# SCH_URM07-Test_2025-04-24.net
KiCad netlist of a schematic drawn in EasyEDA
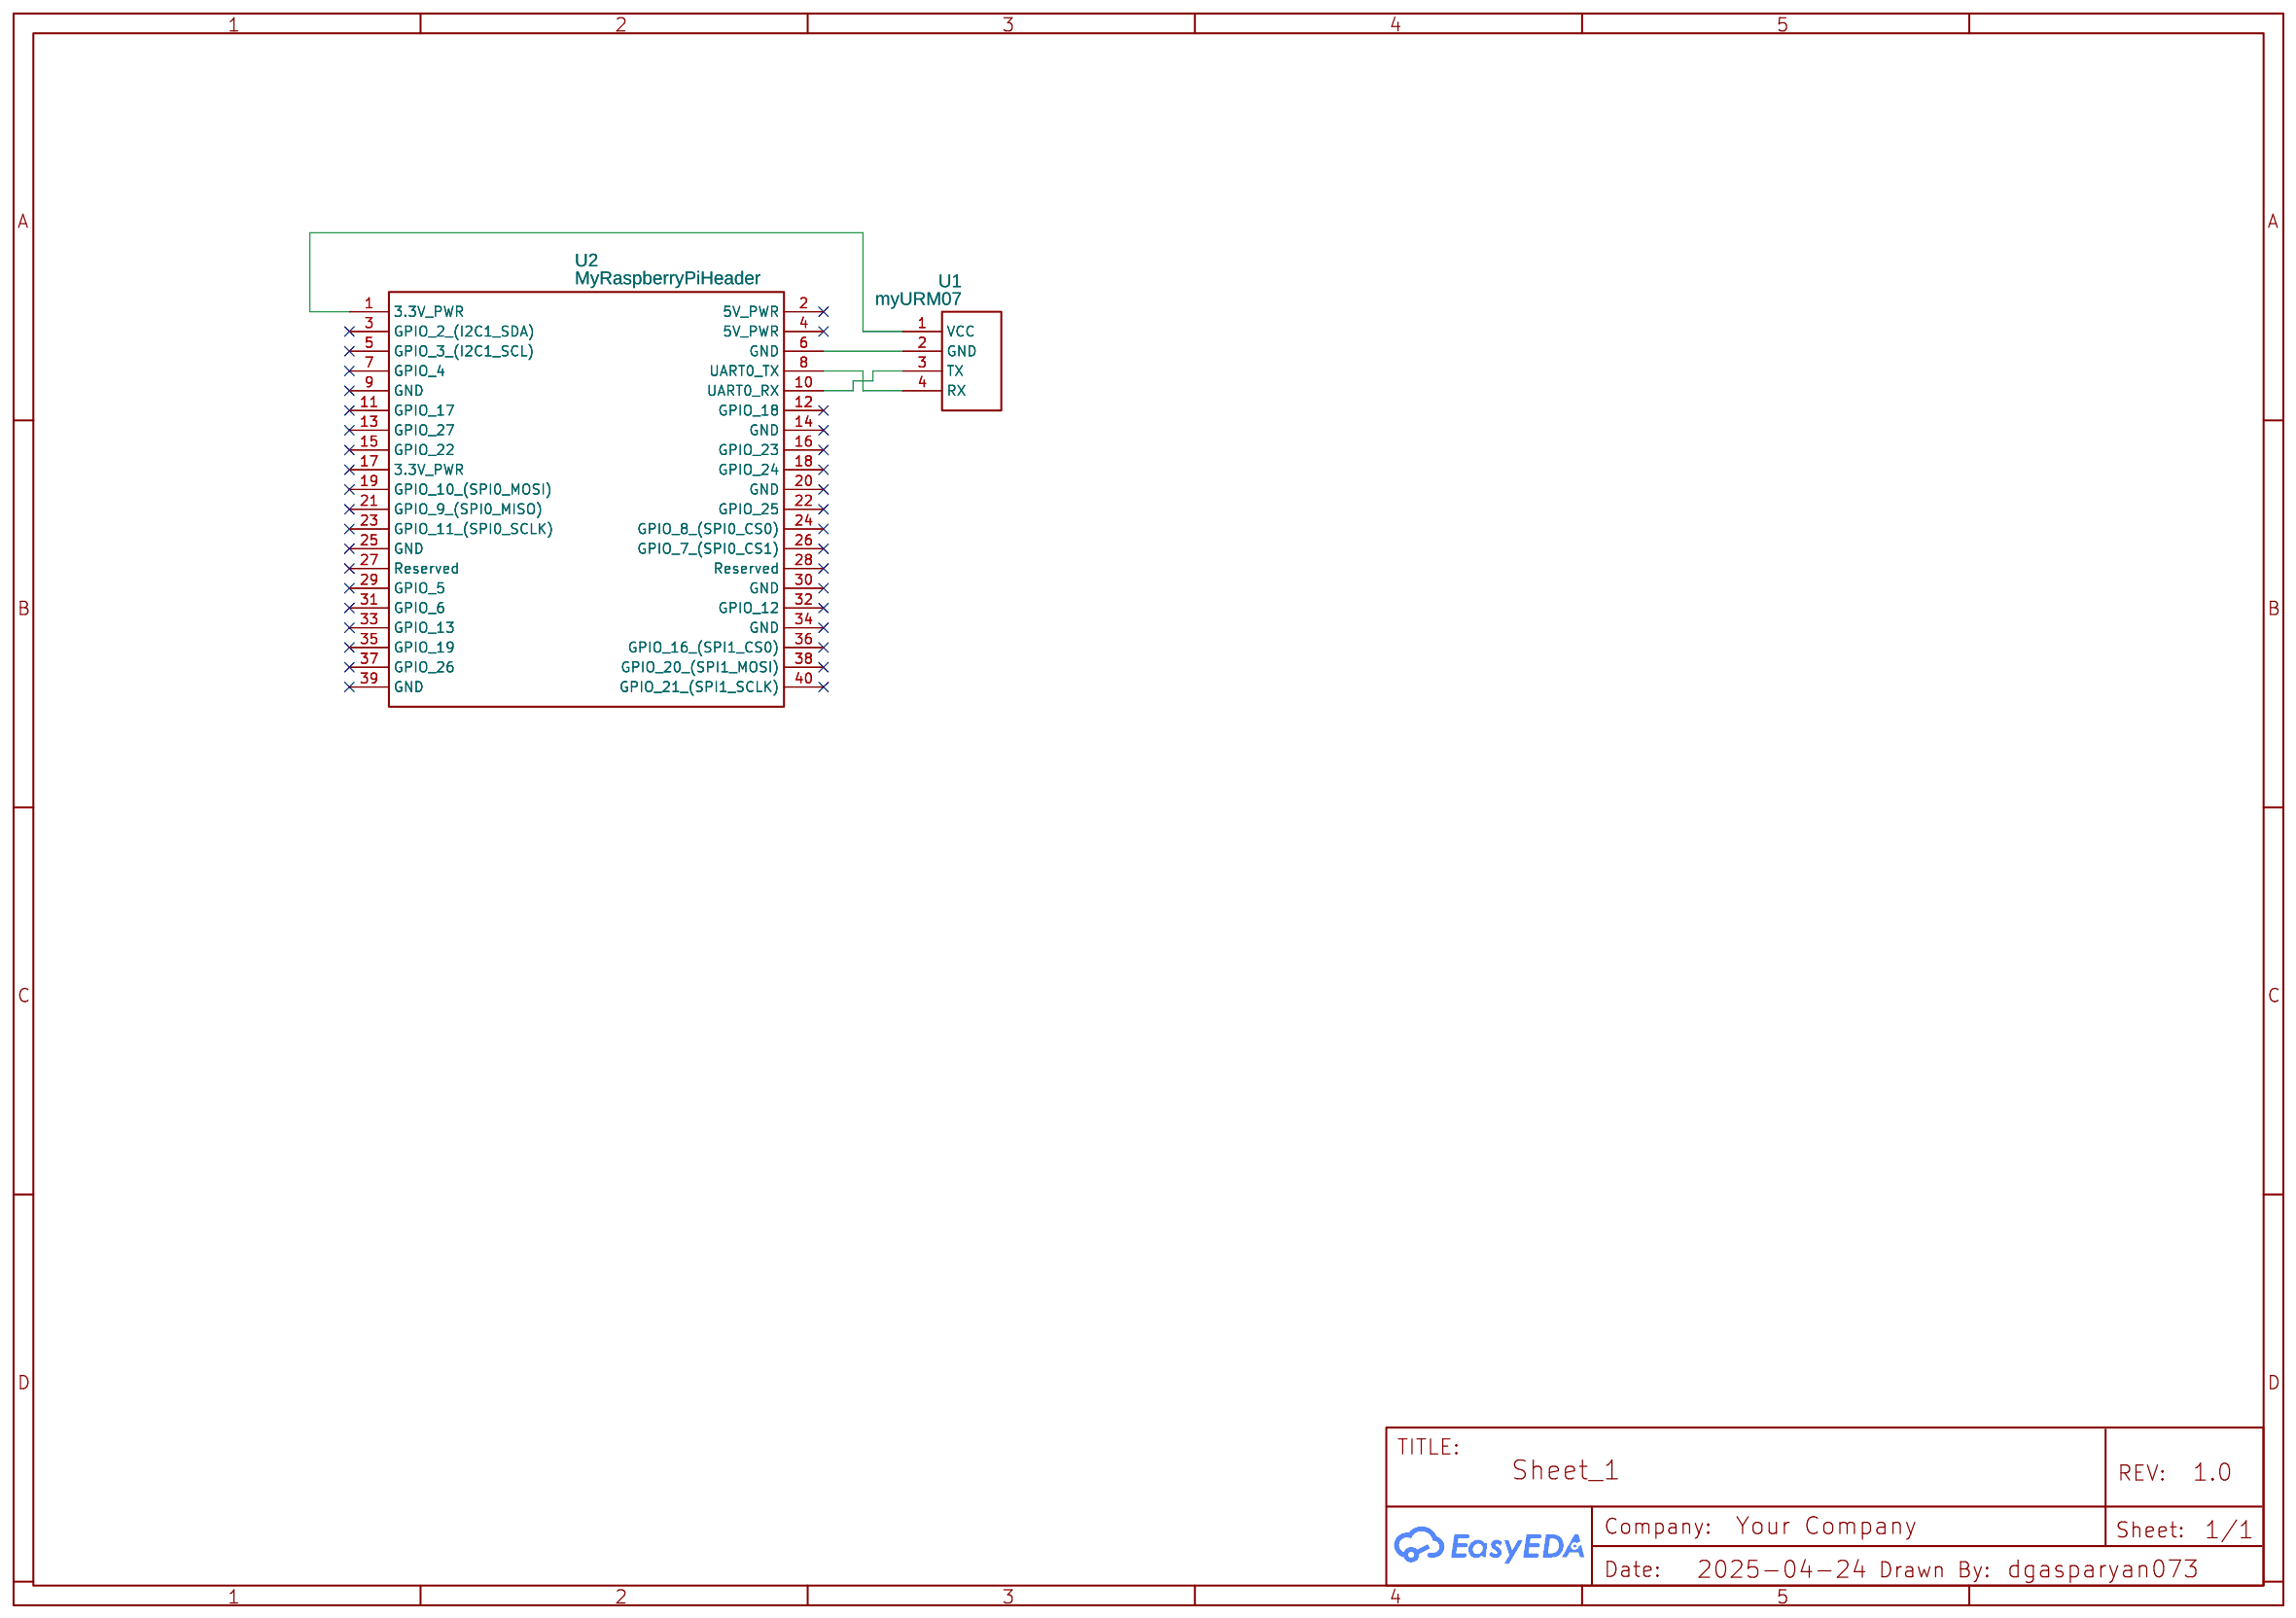
[diagram p0: schematic sheet]

(export (version "E")
  (design (tool "Eeschema 10.0.6"))
  (components
    (comp (ref "U1") (value "myURM07") (libsource (lib "") (part "myURM07")))
    (comp (ref "U2") (value "MyRaspberryPiHeader") (libsource (lib "") (part "MyRaspberryPiHeader")))
  )
  (nets
    (net (code "1") (name "Net-(U1-GND)") (class "Default")
      (node (ref "U1") (pin "2") (pinfunction "GND_2") (pintype "unspecified"))
      (node (ref "U2") (pin "6") (pinfunction "GND_6") (pintype "unspecified"))
    )
    (net (code "2") (name "Net-(U1-RX)") (class "Default")
      (node (ref "U1") (pin "4") (pinfunction "RX_4") (pintype "unspecified"))
      (node (ref "U2") (pin "8") (pinfunction "UART0_TX_8") (pintype "unspecified"))
    )
    (net (code "3") (name "Net-(U1-TX)") (class "Default")
      (node (ref "U1") (pin "3") (pinfunction "TX_3") (pintype "unspecified"))
      (node (ref "U2") (pin "10") (pinfunction "UART0_RX_10") (pintype "unspecified"))
    )
    (net (code "4") (name "Net-(U1-VCC)") (class "Default")
      (node (ref "U1") (pin "1") (pinfunction "VCC_1") (pintype "unspecified"))
      (node (ref "U2") (pin "1") (pinfunction "3.3V_PWR_1") (pintype "unspecified"))
    )
    (net (code "5") (name "unconnected-(U2-3.3V_PWR-Pad17)") (class "Default")
      (node (ref "U2") (pin "17") (pinfunction "3.3V_PWR_17") (pintype "unspecified+no_connect"))
    )
    (net (code "6") (name "unconnected-(U2-5V_PWR-Pad2)") (class "Default")
      (node (ref "U2") (pin "2") (pinfunction "5V_PWR_2") (pintype "unspecified+no_connect"))
    )
    (net (code "7") (name "unconnected-(U2-5V_PWR-Pad4)") (class "Default")
      (node (ref "U2") (pin "4") (pinfunction "5V_PWR_4") (pintype "unspecified+no_connect"))
    )
    (net (code "8") (name "unconnected-(U2-GND-Pad9)") (class "Default")
      (node (ref "U2") (pin "9") (pinfunction "GND_9") (pintype "unspecified+no_connect"))
    )
    (net (code "9") (name "unconnected-(U2-GND-Pad14)") (class "Default")
      (node (ref "U2") (pin "14") (pinfunction "GND_14") (pintype "unspecified+no_connect"))
    )
    (net (code "10") (name "unconnected-(U2-GND-Pad20)") (class "Default")
      (node (ref "U2") (pin "20") (pinfunction "GND_20") (pintype "unspecified+no_connect"))
    )
    (net (code "11") (name "unconnected-(U2-GND-Pad25)") (class "Default")
      (node (ref "U2") (pin "25") (pinfunction "GND_25") (pintype "unspecified+no_connect"))
    )
    (net (code "12") (name "unconnected-(U2-GND-Pad30)") (class "Default")
      (node (ref "U2") (pin "30") (pinfunction "GND_30") (pintype "unspecified+no_connect"))
    )
    (net (code "13") (name "unconnected-(U2-GND-Pad34)") (class "Default")
      (node (ref "U2") (pin "34") (pinfunction "GND_34") (pintype "unspecified+no_connect"))
    )
    (net (code "14") (name "unconnected-(U2-GND-Pad39)") (class "Default")
      (node (ref "U2") (pin "39") (pinfunction "GND_39") (pintype "unspecified+no_connect"))
    )
    (net (code "15") (name "unconnected-(U2-GPIO_2_(I2C1_SDA)-Pad3)") (class "Default")
      (node (ref "U2") (pin "3") (pinfunction "GPIO_2_(I2C1_SDA)_3") (pintype "unspecified+no_connect"))
    )
    (net (code "16") (name "unconnected-(U2-GPIO_3_(I2C1_SCL)-Pad5)") (class "Default")
      (node (ref "U2") (pin "5") (pinfunction "GPIO_3_(I2C1_SCL)_5") (pintype "unspecified+no_connect"))
    )
    (net (code "17") (name "unconnected-(U2-GPIO_4-Pad7)") (class "Default")
      (node (ref "U2") (pin "7") (pinfunction "GPIO_4_7") (pintype "unspecified+no_connect"))
    )
    (net (code "18") (name "unconnected-(U2-GPIO_5-Pad29)") (class "Default")
      (node (ref "U2") (pin "29") (pinfunction "GPIO_5_29") (pintype "unspecified+no_connect"))
    )
    (net (code "19") (name "unconnected-(U2-GPIO_6-Pad31)") (class "Default")
      (node (ref "U2") (pin "31") (pinfunction "GPIO_6_31") (pintype "unspecified+no_connect"))
    )
    (net (code "20") (name "unconnected-(U2-GPIO_7_(SPI0_CS1)-Pad26)") (class "Default")
      (node (ref "U2") (pin "26") (pinfunction "GPIO_7_(SPI0_CS1)_26") (pintype "unspecified+no_connect"))
    )
    (net (code "21") (name "unconnected-(U2-GPIO_8_(SPI0_CS0)-Pad24)") (class "Default")
      (node (ref "U2") (pin "24") (pinfunction "GPIO_8_(SPI0_CS0)_24") (pintype "unspecified+no_connect"))
    )
    (net (code "22") (name "unconnected-(U2-GPIO_9_(SPI0_MISO)-Pad21)") (class "Default")
      (node (ref "U2") (pin "21") (pinfunction "GPIO_9_(SPI0_MISO)_21") (pintype "unspecified+no_connect"))
    )
    (net (code "23") (name "unconnected-(U2-GPIO_10_(SPI0_MOSI)-Pad19)") (class "Default")
      (node (ref "U2") (pin "19") (pinfunction "GPIO_10_(SPI0_MOSI)_19") (pintype "unspecified+no_connect"))
    )
    (net (code "24") (name "unconnected-(U2-GPIO_11_(SPI0_SCLK)-Pad23)") (class "Default")
      (node (ref "U2") (pin "23") (pinfunction "GPIO_11_(SPI0_SCLK)_23") (pintype "unspecified+no_connect"))
    )
    (net (code "25") (name "unconnected-(U2-GPIO_12-Pad32)") (class "Default")
      (node (ref "U2") (pin "32") (pinfunction "GPIO_12_32") (pintype "unspecified+no_connect"))
    )
    (net (code "26") (name "unconnected-(U2-GPIO_13-Pad33)") (class "Default")
      (node (ref "U2") (pin "33") (pinfunction "GPIO_13_33") (pintype "unspecified+no_connect"))
    )
    (net (code "27") (name "unconnected-(U2-GPIO_16_(SPI1_CS0)-Pad36)") (class "Default")
      (node (ref "U2") (pin "36") (pinfunction "GPIO_16_(SPI1_CS0)_36") (pintype "unspecified+no_connect"))
    )
    (net (code "28") (name "unconnected-(U2-GPIO_17-Pad11)") (class "Default")
      (node (ref "U2") (pin "11") (pinfunction "GPIO_17_11") (pintype "unspecified+no_connect"))
    )
    (net (code "29") (name "unconnected-(U2-GPIO_18-Pad12)") (class "Default")
      (node (ref "U2") (pin "12") (pinfunction "GPIO_18_12") (pintype "unspecified+no_connect"))
    )
    (net (code "30") (name "unconnected-(U2-GPIO_19-Pad35)") (class "Default")
      (node (ref "U2") (pin "35") (pinfunction "GPIO_19_35") (pintype "unspecified+no_connect"))
    )
    (net (code "31") (name "unconnected-(U2-GPIO_20_(SPI1_MOSI)-Pad38)") (class "Default")
      (node (ref "U2") (pin "38") (pinfunction "GPIO_20_(SPI1_MOSI)_38") (pintype "unspecified+no_connect"))
    )
    (net (code "32") (name "unconnected-(U2-GPIO_21_(SPI1_SCLK)-Pad40)") (class "Default")
      (node (ref "U2") (pin "40") (pinfunction "GPIO_21_(SPI1_SCLK)_40") (pintype "unspecified+no_connect"))
    )
    (net (code "33") (name "unconnected-(U2-GPIO_22-Pad15)") (class "Default")
      (node (ref "U2") (pin "15") (pinfunction "GPIO_22_15") (pintype "unspecified+no_connect"))
    )
    (net (code "34") (name "unconnected-(U2-GPIO_23-Pad16)") (class "Default")
      (node (ref "U2") (pin "16") (pinfunction "GPIO_23_16") (pintype "unspecified+no_connect"))
    )
    (net (code "35") (name "unconnected-(U2-GPIO_24-Pad18)") (class "Default")
      (node (ref "U2") (pin "18") (pinfunction "GPIO_24_18") (pintype "unspecified+no_connect"))
    )
    (net (code "36") (name "unconnected-(U2-GPIO_25-Pad22)") (class "Default")
      (node (ref "U2") (pin "22") (pinfunction "GPIO_25_22") (pintype "unspecified+no_connect"))
    )
    (net (code "37") (name "unconnected-(U2-GPIO_26-Pad37)") (class "Default")
      (node (ref "U2") (pin "37") (pinfunction "GPIO_26_37") (pintype "unspecified+no_connect"))
    )
    (net (code "38") (name "unconnected-(U2-GPIO_27-Pad13)") (class "Default")
      (node (ref "U2") (pin "13") (pinfunction "GPIO_27_13") (pintype "unspecified+no_connect"))
    )
    (net (code "39") (name "unconnected-(U2-Reserved-Pad27)") (class "Default")
      (node (ref "U2") (pin "27") (pinfunction "Reserved_27") (pintype "unspecified+no_connect"))
    )
    (net (code "40") (name "unconnected-(U2-Reserved-Pad28)") (class "Default")
      (node (ref "U2") (pin "28") (pinfunction "Reserved_28") (pintype "unspecified+no_connect"))
    )
  )
)
